# USB.net
KiCad netlist of a schematic drawn in Altium Designer
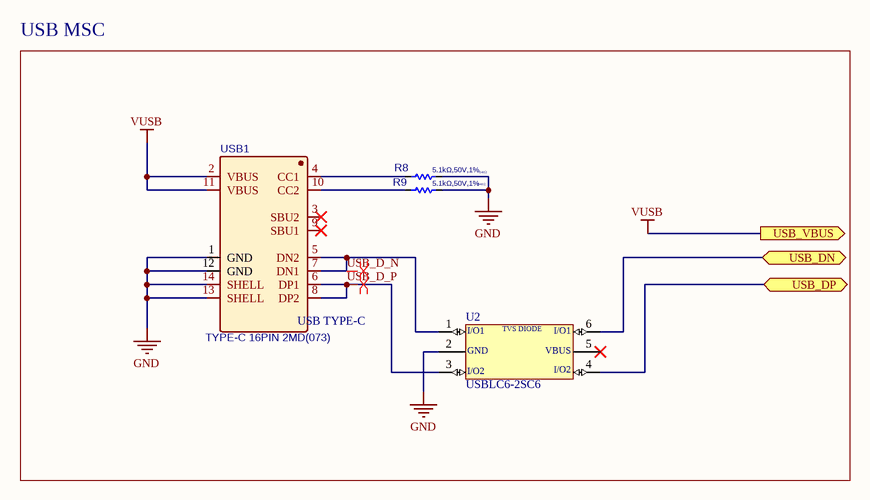
[diagram p0: USB.SchDoc]

(export (version "E")
  (design (tool "Eeschema 10.0.6"))
  (components
    (comp (ref "R8")
      (value "5.1kΩ,50V,1%")
      (footprint "R0402")
      (description "100mW Thick Film Resistors 75V ±100ppm/℃ ±1% 100kΩ 0603 Chip Resistor - Surface Mount ROHS")
      (fields
        (field (name "MPN") "RC0402FR-075K1L")
        (field (name "MANUFACTURER") "YAGEO")
        (field (name "PACKAGE") "0402")
      )
      (libsource (lib "RCL") (part "RC0402FR-075K1L"))
    )
    (comp (ref "R9")
      (value "5.1kΩ,50V,1%")
      (footprint "R0402")
      (description "100mW Thick Film Resistors 75V ±100ppm/℃ ±1% 100kΩ 0603 Chip Resistor - Surface Mount ROHS")
      (fields
        (field (name "MPN") "RC0402FR-075K1L")
        (field (name "MANUFACTURER") "YAGEO")
        (field (name "PACKAGE") "0402")
      )
      (libsource (lib "RCL") (part "RC0402FR-075K1L"))
    )
    (comp (ref "U2")
      (value "USBLC6-2SC6")
      (footprint "SOT95P280X145-6N")
      (description "17V Clamp 5A (8/20Âµs) Ipp Tvs Diode Surface Mount SOT-23-6")
      (fields (field (name "MF") "STMicroelectronics"))
      (libsource (lib "IC") (part "USBLC6-2SC6"))
    )
    (comp (ref "USB1")
      (value "TYPE-C 16PIN 2MD(073)")
      (footprint "TYPE-C 16PIN 2MD(073)")
      (description "5A 1 Surface Mount 16P Female -25℃~+85℃ Type-C SMD USB Connectors ROHS")
      (fields (field (name "MANUFACTURER") "SHOU HAN(首韩)"))
      (libsource (lib "connector_button") (part "TYPE-C 16PIN 2MD(073)"))
    )
  )
  (nets
    (net (code "1") (name "/USB_DN") (class "Default")
      (node (ref "U2") (pin "6") (pinfunction "I/O1_OUT_6") (pintype "bidirectional"))
    )
    (net (code "2") (name "/USB_DP") (class "Default")
      (node (ref "U2") (pin "4") (pinfunction "I/O2_OUT_4") (pintype "bidirectional"))
    )
    (net (code "3") (name "/USB_D_N") (class "Default")
      (node (ref "U2") (pin "1") (pinfunction "I/O1_IN_1") (pintype "bidirectional"))
      (node (ref "USB1") (pin "5") (pinfunction "DN2_5") (pintype "passive"))
      (node (ref "USB1") (pin "7") (pinfunction "DN1_7") (pintype "passive"))
    )
    (net (code "4") (name "/USB_D_P") (class "Default")
      (node (ref "U2") (pin "3") (pinfunction "I/O2_IN_3") (pintype "bidirectional"))
      (node (ref "USB1") (pin "6") (pinfunction "DP1_6") (pintype "passive"))
      (node (ref "USB1") (pin "8") (pinfunction "DP2_8") (pintype "passive"))
    )
    (net (code "5") (name "GND") (class "Default")
      (node (ref "R8") (pin "2") (pinfunction "2_2") (pintype "passive"))
      (node (ref "R9") (pin "2") (pinfunction "2_2") (pintype "passive"))
      (node (ref "U2") (pin "2") (pinfunction "GND_2") (pintype "power_in"))
      (node (ref "USB1") (pin "1") (pinfunction "GND_1") (pintype "passive"))
      (node (ref "USB1") (pin "12") (pinfunction "GND_12") (pintype "passive"))
      (node (ref "USB1") (pin "13") (pinfunction "SHELL_13") (pintype "passive"))
      (node (ref "USB1") (pin "14") (pinfunction "SHELL_14") (pintype "passive"))
    )
    (net (code "6") (name "Net-(USB1-CC1)") (class "Default")
      (node (ref "R8") (pin "1") (pinfunction "1_1") (pintype "passive"))
      (node (ref "USB1") (pin "4") (pinfunction "CC1_4") (pintype "passive"))
    )
    (net (code "7") (name "Net-(USB1-CC2)") (class "Default")
      (node (ref "R9") (pin "1") (pinfunction "1_1") (pintype "passive"))
      (node (ref "USB1") (pin "10") (pinfunction "CC2_10") (pintype "passive"))
    )
    (net (code "8") (name "VUSB") (class "Default")
      (node (ref "USB1") (pin "11") (pinfunction "VBUS_11") (pintype "passive"))
      (node (ref "USB1") (pin "2") (pinfunction "VBUS_2") (pintype "passive"))
    )
    (net (code "9") (name "unconnected-(U2-VBUS-Pad5)") (class "Default")
      (node (ref "U2") (pin "5") (pinfunction "VBUS_5") (pintype "power_in+no_connect"))
    )
    (net (code "10") (name "unconnected-(USB1-SBU1-Pad9)") (class "Default")
      (node (ref "USB1") (pin "9") (pinfunction "SBU1_9") (pintype "passive+no_connect"))
    )
    (net (code "11") (name "unconnected-(USB1-SBU2-Pad3)") (class "Default")
      (node (ref "USB1") (pin "3") (pinfunction "SBU2_3") (pintype "passive+no_connect"))
    )
  )
)
